# microSDHC_SPI.net
KiCad netlist of a schematic drawn in Altium Designer
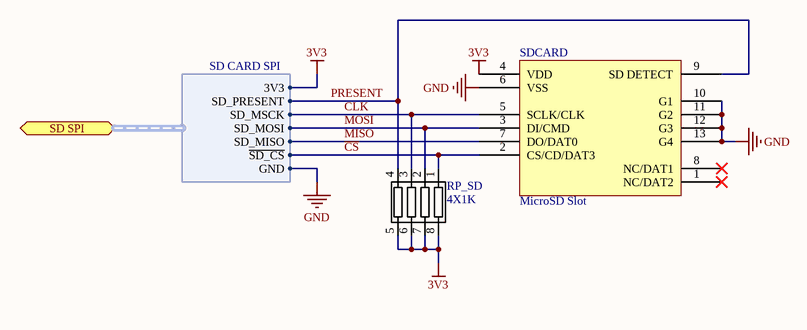
[diagram p0: microSDHC_SPI.SchDoc]

(export (version "E")
  (design (tool "Eeschema 10.0.6"))
  (components
    (comp (ref "RP_SD")
      (value "4X1K")
      (footprint "1206-ARRAY-4")
      (description "GENERIC RESISTOR ARRAY 4X INDEPENDENT")
      (fields (field (name "MANUFACTURER PART NUMBER") "MNR14E0APJ101") (field (name "TOLERANCE") "±5%"))
      (libsource (lib "vh_altium_library") (part "ARRAY4-100R-ROHM"))
    )
    (comp (ref "SDCARD")
      (value "MicroSD Slot")
      (footprint "MICROSD Slot")
      (libsource (lib "AltiumLib1") (part "MicroSD Slot"))
    )
  )
  (nets
    (net (code "4") (name "/CLK") (class "Default")
      (node (ref "RP_SD") (pin "3") (pintype "passive"))
      (node (ref "SDCARD") (pin "5") (pinfunction "SCLK/CLK_5") (pintype "passive"))
    )
    (net (code "5") (name "/MISO") (class "Default")
      (node (ref "SDCARD") (pin "7") (pinfunction "DO/DAT0_7") (pintype "passive"))
    )
    (net (code "6") (name "/MOSI") (class "Default")
      (node (ref "RP_SD") (pin "2") (pintype "passive"))
      (node (ref "SDCARD") (pin "3") (pinfunction "DI/CMD_3") (pintype "passive"))
    )
    (net (code "7") (name "/PRESENT") (class "Default")
      (node (ref "RP_SD") (pin "4") (pintype "passive"))
      (node (ref "SDCARD") (pin "9") (pinfunction "SD_DETECT_9") (pintype "passive"))
    )
    (net (code "9") (name "/~{CS}") (class "Default")
      (node (ref "RP_SD") (pin "1") (pintype "passive"))
      (node (ref "SDCARD") (pin "2") (pinfunction "CS/CD/DAT3_2") (pintype "passive"))
    )
    (net (code "10") (name "3V3") (class "Default")
      (node (ref "RP_SD") (pin "5") (pintype "passive"))
      (node (ref "RP_SD") (pin "6") (pintype "passive"))
      (node (ref "RP_SD") (pin "7") (pintype "passive"))
      (node (ref "RP_SD") (pin "8") (pintype "passive"))
      (node (ref "SDCARD") (pin "4") (pinfunction "VDD_4") (pintype "passive"))
    )
    (net (code "11") (name "GND") (class "Default")
      (node (ref "SDCARD") (pin "10") (pinfunction "G1_10") (pintype "passive"))
      (node (ref "SDCARD") (pin "11") (pinfunction "G2_11") (pintype "passive"))
      (node (ref "SDCARD") (pin "12") (pinfunction "G3_12") (pintype "passive"))
      (node (ref "SDCARD") (pin "13") (pinfunction "G4_13") (pintype "passive"))
      (node (ref "SDCARD") (pin "6") (pinfunction "VSS_6") (pintype "passive"))
    )
    (net (code "12") (name "unconnected-(SDCARD-NC{slash}DAT1-Pad8)") (class "Default")
      (node (ref "SDCARD") (pin "8") (pinfunction "NC/DAT1_8") (pintype "passive+no_connect"))
    )
    (net (code "13") (name "unconnected-(SDCARD-NC{slash}DAT2-Pad1)") (class "Default")
      (node (ref "SDCARD") (pin "1") (pinfunction "NC/DAT2_1") (pintype "passive+no_connect"))
    )
  )
)
